# pest_repeller.net
KiCad netlist of a schematic drawn in EAGLE
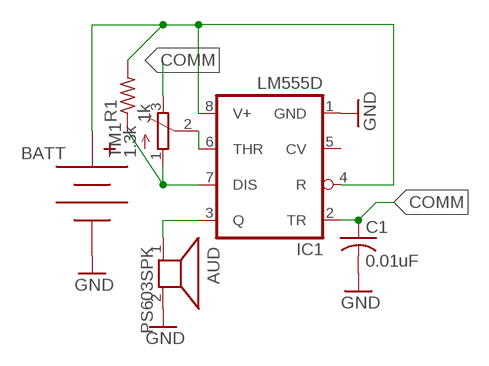
[diagram p0: schematic, sheet 1]

(export (version "E")
  (design (tool "Eeschema 10.0.6"))
  (components
    (comp (ref "AUD")
      (value "PS603SPK")
      (footprint "eagle-import:PS603")
      (fields (field (name "MPN") "MCKPSP2950PN-16/0.25A-4763"))
      (libsource (lib "eagle-import") (part "PS603SPK"))
    )
    (comp (ref "BATT")
      (value "BC9VPC")
      (footprint "eagle-import:BC9VPC")
      (fields (field (name "MF") "KEYSTONE ELECTR") (field (name "MPN") "96"))
      (libsource (lib "eagle-import") (part "BC9VPC"))
    )
    (comp (ref "C1")
      (value "0.01uF")
      (footprint "eagle-import:C0805")
      (fields (field (name "MPN") "C0805J103K3RACAUTO"))
      (libsource (lib "eagle-import") (part "C-USC0805"))
    )
    (comp (ref "IC1")
      (value "LM555D")
      (footprint "eagle-import:SO08")
      (fields (field (name "MPN") "TLC555CP"))
      (libsource (lib "eagle-import") (part "555DLM"))
    )
    (comp (ref "R1")
      (value "1k")
      (footprint "eagle-import:R0805")
      (fields (field (name "MF") "BOURNS, INC.") (field (name "MPN") "CR0805-FX-1001ELF"))
      (libsource (lib "eagle-import") (part "R-US_R0805"))
    )
    (comp (ref "TM1")
      (value "1.3k")
      (footprint "eagle-import:TC33X")
      (fields (field (name "MF") "BOURNS, INC.") (field (name "MPN") "3306F-1-103"))
      (libsource (lib "eagle-import") (part "TRIMPOTTC33X"))
    )
  )
  (nets
    (net (code "1") (name "COMM") (class "Default")
      (node (ref "C1") (pin "1") (pinfunction "1_1") (pintype "passive"))
      (node (ref "IC1") (pin "2") (pinfunction "TR_2") (pintype "input"))
      (node (ref "TM1") (pin "3") (pinfunction "E_3") (pintype "passive"))
    )
    (net (code "2") (name "GND") (class "Default")
      (node (ref "AUD") (pin "2") (pinfunction "2_2") (pintype "passive"))
      (node (ref "BATT") (pin "V-") (pinfunction "V-_V-") (pintype "bidirectional"))
      (node (ref "C1") (pin "2") (pinfunction "2_2") (pintype "passive"))
      (node (ref "IC1") (pin "1") (pinfunction "GND_1") (pintype "power_in"))
    )
    (net (code "3") (name "Net-(IC1-DIS)") (class "Default")
      (node (ref "IC1") (pin "7") (pinfunction "DIS_7") (pintype "input"))
      (node (ref "R1") (pin "1") (pinfunction "1_1") (pintype "passive"))
      (node (ref "TM1") (pin "1") (pinfunction "A_1") (pintype "passive"))
    )
    (net (code "4") (name "Net-(IC1-Q)") (class "Default")
      (node (ref "AUD") (pin "1") (pinfunction "1_1") (pintype "passive"))
      (node (ref "IC1") (pin "3") (pinfunction "Q_3") (pintype "output"))
    )
    (net (code "5") (name "Net-(IC1-R)") (class "Default")
      (node (ref "BATT") (pin "V+") (pinfunction "V+_V+") (pintype "bidirectional"))
      (node (ref "IC1") (pin "4") (pinfunction "R_4") (pintype "input"))
      (node (ref "IC1") (pin "8") (pinfunction "V+_8") (pintype "power_in"))
      (node (ref "R1") (pin "2") (pinfunction "2_2") (pintype "passive"))
    )
    (net (code "6") (name "Net-(IC1-THR)") (class "Default")
      (node (ref "IC1") (pin "6") (pinfunction "THR_6") (pintype "input"))
      (node (ref "TM1") (pin "2") (pinfunction "S_2") (pintype "passive"))
    )
    (net (code "7") (name "unconnected-(IC1-CV-Pad5)") (class "Default")
      (node (ref "IC1") (pin "5") (pinfunction "CV_5") (pintype "input"))
    )
  )
)
